# Eye-of-Ord-v1_10.net
KiCad netlist of a schematic drawn in EAGLE
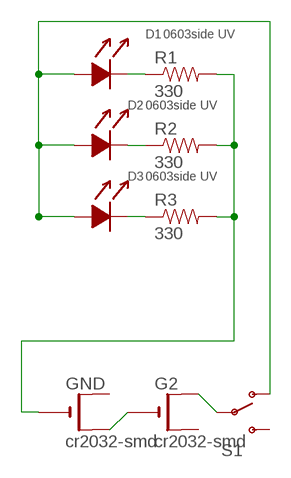
[diagram p0: schematic, sheet 1]

(export (version "E")
  (design (tool "Eeschema 10.0.6"))
  (components
    (comp (ref "D1")
      (value "0603side UV")
      (footprint "eagle-import:SMD-0603-LED-SIDE")
      (libsource (lib "eagle-import") (part "0603SIDELED"))
    )
    (comp (ref "D2")
      (value "0603side UV")
      (footprint "eagle-import:SMD-0603-LED-SIDE")
      (libsource (lib "eagle-import") (part "0603SIDELED"))
    )
    (comp (ref "D3")
      (value "0603side UV")
      (footprint "eagle-import:SMD-0603-LED-SIDE")
      (libsource (lib "eagle-import") (part "0603SIDELED"))
    )
    (comp (ref "G2")
      (value "cr2032-smd")
      (footprint "eagle-import:CR2032-SMD")
      (libsource (lib "eagle-import") (part "CR2032SMT"))
    )
    (comp (ref "GND")
      (value "cr2032-smd")
      (footprint "eagle-import:CR2032-SMD")
      (libsource (lib "eagle-import") (part "CR2032SMT"))
    )
    (comp (ref "R1")
      (value "330")
      (footprint "eagle-import:0603-RES")
      (libsource (lib "eagle-import") (part "RESISTOR0603-RES"))
    )
    (comp (ref "R2")
      (value "330")
      (footprint "eagle-import:0603-RES")
      (libsource (lib "eagle-import") (part "RESISTOR0603-RES"))
    )
    (comp (ref "R3")
      (value "330")
      (footprint "eagle-import:0603-RES")
      (libsource (lib "eagle-import") (part "RESISTOR0603-RES"))
    )
    (comp (ref "S1")
      (value "SWITCH-SPDT-SMD-A")
      (footprint "eagle-import:SWITCH-SPST-SMD-A")
      (libsource (lib "eagle-import") (part "SWITCH-SPDT-SMD-A"))
    )
  )
  (nets
    (net (code "1") (name "Net-(D1-K)") (class "Default")
      (node (ref "D1") (pin "C") (pinfunction "K_C") (pintype "bidirectional"))
      (node (ref "R1") (pin "1") (pinfunction "1_1") (pintype "passive"))
    )
    (net (code "2") (name "Net-(D2-K)") (class "Default")
      (node (ref "D2") (pin "C") (pinfunction "K_C") (pintype "bidirectional"))
      (node (ref "R2") (pin "1") (pinfunction "1_1") (pintype "passive"))
    )
    (net (code "3") (name "Net-(D3-K)") (class "Default")
      (node (ref "D3") (pin "C") (pinfunction "K_C") (pintype "bidirectional"))
      (node (ref "R3") (pin "1") (pinfunction "1_1") (pintype "passive"))
    )
    (net (code "4") (name "Net-(G2-+)") (class "Default")
      (node (ref "G2") (pin "+$1") (pinfunction "+_+$1") (pintype "passive"))
      (node (ref "S1") (pin "2") (pinfunction "P_2") (pintype "passive"))
    )
    (net (code "5") (name "Net-(GND-+1)") (class "Default")
      (node (ref "G2") (pin "-") (pinfunction "-_-") (pintype "passive"))
      (node (ref "GND") (pin "+$2") (pinfunction "+1_+$2") (pintype "passive"))
    )
    (net (code "6") (name "Net-(GND-Pad-)") (class "Default")
      (node (ref "GND") (pin "-") (pinfunction "-_-") (pintype "passive"))
      (node (ref "R1") (pin "2") (pinfunction "2_2") (pintype "passive"))
      (node (ref "R2") (pin "2") (pinfunction "2_2") (pintype "passive"))
      (node (ref "R3") (pin "2") (pinfunction "2_2") (pintype "passive"))
    )
    (net (code "7") (name "Net-(S1-O)") (class "Default")
      (node (ref "D1") (pin "A") (pinfunction "A_A") (pintype "bidirectional"))
      (node (ref "D2") (pin "A") (pinfunction "A_A") (pintype "bidirectional"))
      (node (ref "D3") (pin "A") (pinfunction "A_A") (pintype "bidirectional"))
      (node (ref "S1") (pin "1") (pinfunction "O_1") (pintype "passive"))
    )
    (net (code "8") (name "unconnected-(G2-+1-Pad+$2)") (class "Default")
      (node (ref "G2") (pin "+$2") (pinfunction "+1_+$2") (pintype "passive"))
    )
    (net (code "9") (name "unconnected-(GND-+-Pad+$1)") (class "Default")
      (node (ref "GND") (pin "+$1") (pinfunction "+_+$1") (pintype "passive"))
    )
    (net (code "10") (name "unconnected-(S1-S-Pad3)") (class "Default")
      (node (ref "S1") (pin "3") (pinfunction "S_3") (pintype "passive"))
    )
  )
)
